# Connectors.net
KiCad netlist of a schematic drawn in Altium Designer
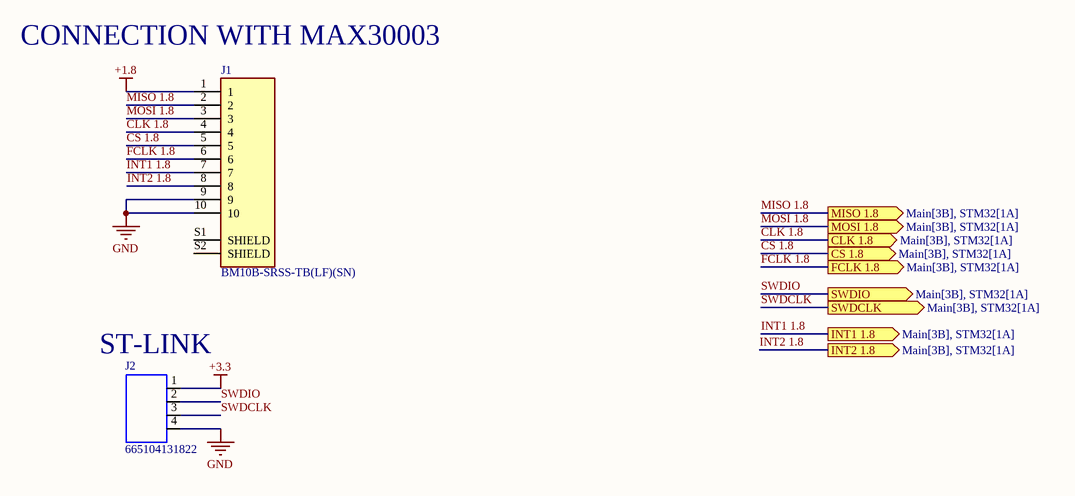
[diagram p0: Connectors.SchDoc]

(export (version "E")
  (design (tool "Eeschema 10.0.6"))
  (components
    (comp (ref "J1")
      (value "BM10B-SRSS-TB(LF)(SN)")
      (footprint "JST_BM10B-SRSS-TB(LF)(SN)")
      (description "Connector Header Surface Mount 10 position 0.039 (1.00mm)")
      (fields (field (name "MF") "JST Sales"))
      (libsource (lib "BM10B-SRSS-TB_LF__SN_") (part "BM10B-SRSS-TB(LF)(SN)"))
    )
    (comp (ref "J2")
      (value "665104131822")
      (footprint "SnapEDApcb:665104131822")
      (description "Connector Header Surface Mount, Right Angle 4 position 0.039 (1.00mm)")
      (fields (field (name "MF") "Wurth Electronics"))
      (libsource (lib "SnapEDAsch") (part "665104131822"))
    )
  )
  (nets
    (net (code "1") (name "+1.8") (class "Default")
      (node (ref "J1") (pin "1") (pinfunction "1_1") (pintype "passive"))
    )
    (net (code "2") (name "+3.3") (class "Default")
      (node (ref "J2") (pin "1") (pinfunction "4_1") (pintype "passive"))
    )
    (net (code "3") (name "/CLK 1.8") (class "Default")
      (node (ref "J1") (pin "4") (pinfunction "4_4") (pintype "passive"))
    )
    (net (code "4") (name "/CS 1.8") (class "Default")
      (node (ref "J1") (pin "5") (pinfunction "5_5") (pintype "passive"))
    )
    (net (code "5") (name "/FCLK 1.8") (class "Default")
      (node (ref "J1") (pin "6") (pinfunction "6_6") (pintype "passive"))
    )
    (net (code "6") (name "/INT1 1.8") (class "Default")
      (node (ref "J1") (pin "7") (pinfunction "7_7") (pintype "passive"))
    )
    (net (code "7") (name "/INT2 1.8") (class "Default")
      (node (ref "J1") (pin "8") (pinfunction "8_8") (pintype "passive"))
    )
    (net (code "8") (name "/MISO 1.8") (class "Default")
      (node (ref "J1") (pin "2") (pinfunction "2_2") (pintype "passive"))
    )
    (net (code "9") (name "/MOSI 1.8") (class "Default")
      (node (ref "J1") (pin "3") (pinfunction "3_3") (pintype "passive"))
    )
    (net (code "10") (name "/SWDCLK") (class "Default")
      (node (ref "J2") (pin "3") (pinfunction "2_3") (pintype "passive"))
    )
    (net (code "11") (name "/SWDIO") (class "Default")
      (node (ref "J2") (pin "2") (pinfunction "3_2") (pintype "passive"))
    )
    (net (code "12") (name "GND") (class "Default")
      (node (ref "J1") (pin "10") (pinfunction "10_10") (pintype "passive"))
      (node (ref "J1") (pin "9") (pinfunction "9_9") (pintype "passive"))
      (node (ref "J2") (pin "4") (pinfunction "1_4") (pintype "passive"))
    )
    (net (code "13") (name "unconnected-(J1-SHIELD-PadS1)") (class "Default")
      (node (ref "J1") (pin "S1") (pinfunction "SHIELD_S1") (pintype "passive"))
    )
    (net (code "14") (name "unconnected-(J1-SHIELD-PadS2)") (class "Default")
      (node (ref "J1") (pin "S2") (pinfunction "SHIELD_S2") (pintype "passive"))
    )
  )
)
